# Stick_IMUinator_v2_1.net
KiCad netlist of a schematic drawn in EAGLE
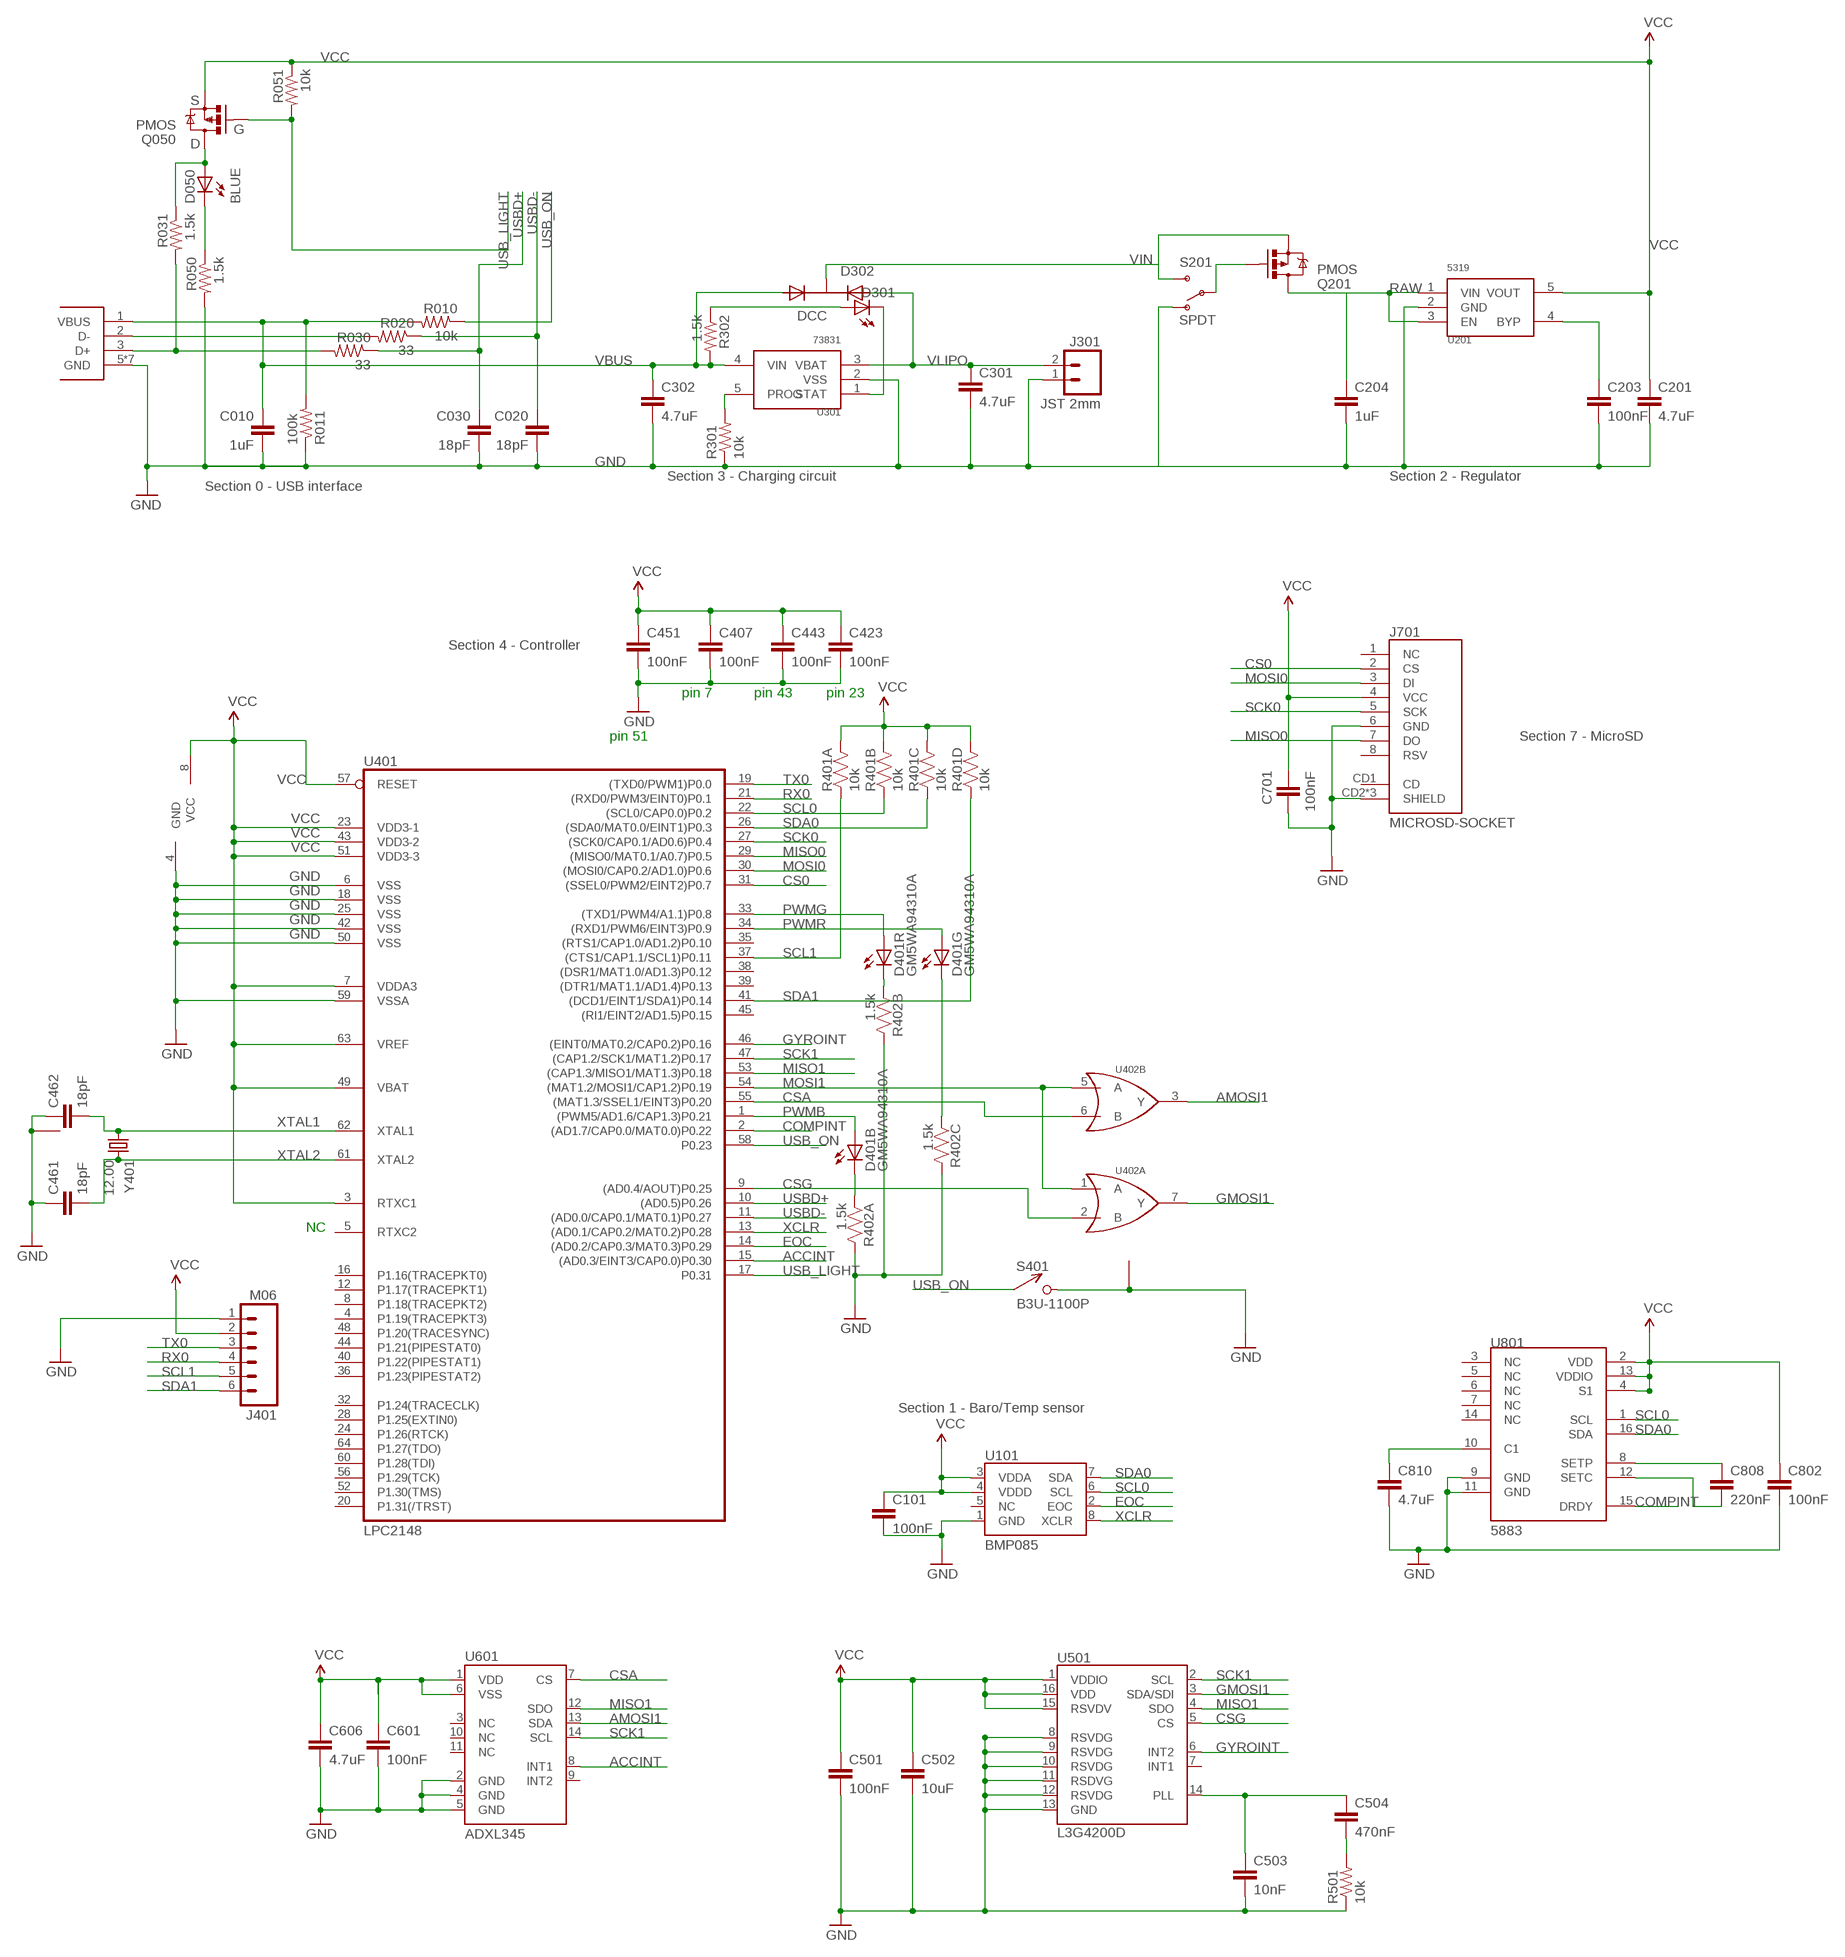
[diagram p0: schematic, sheet 1]

(export (version "E")
  (design (tool "Eeschema 10.0.6"))
  (components
    (comp (ref "C010")
      (value "1uF")
      (footprint "eagle-import:0402-CAP")
      (libsource (lib "eagle-import") (part "CAP0402-CAP"))
    )
    (comp (ref "C020")
      (value "18pF")
      (footprint "eagle-import:0402-CAP")
      (libsource (lib "eagle-import") (part "CAP0402-CAP"))
    )
    (comp (ref "C030")
      (value "18pF")
      (footprint "eagle-import:0402-CAP")
      (libsource (lib "eagle-import") (part "CAP0402-CAP"))
    )
    (comp (ref "C101")
      (value "100nF")
      (footprint "eagle-import:0402-CAP")
      (libsource (lib "eagle-import") (part "CAP0402-CAP"))
    )
    (comp (ref "C201")
      (value "4.7uF")
      (footprint "eagle-import:0402-CAP")
      (libsource (lib "eagle-import") (part "CAP0402-CAP"))
    )
    (comp (ref "C203")
      (value "100nF")
      (footprint "eagle-import:0402-CAP")
      (libsource (lib "eagle-import") (part "CAP0402-CAP"))
    )
    (comp (ref "C204")
      (value "1uF")
      (footprint "eagle-import:0402-CAP")
      (libsource (lib "eagle-import") (part "CAP0402-CAP"))
    )
    (comp (ref "C301")
      (value "4.7uF")
      (footprint "eagle-import:0402-CAP")
      (libsource (lib "eagle-import") (part "CAP0402-CAP"))
    )
    (comp (ref "C302")
      (value "4.7uF")
      (footprint "eagle-import:0402-CAP")
      (libsource (lib "eagle-import") (part "CAP0402-CAP"))
    )
    (comp (ref "C407")
      (value "100nF")
      (footprint "eagle-import:0402-CAP")
      (libsource (lib "eagle-import") (part "CAP0402-CAP"))
    )
    (comp (ref "C423")
      (value "100nF")
      (footprint "eagle-import:0402-CAP")
      (libsource (lib "eagle-import") (part "CAP0402-CAP"))
    )
    (comp (ref "C443")
      (value "100nF")
      (footprint "eagle-import:0402-CAP")
      (libsource (lib "eagle-import") (part "CAP0402-CAP"))
    )
    (comp (ref "C451")
      (value "100nF")
      (footprint "eagle-import:0402-CAP")
      (libsource (lib "eagle-import") (part "CAP0402-CAP"))
    )
    (comp (ref "C461")
      (value "18pF")
      (footprint "eagle-import:0402-CAP")
      (libsource (lib "eagle-import") (part "CAP0402-CAP"))
    )
    (comp (ref "C462")
      (value "18pF")
      (footprint "eagle-import:0402-CAP")
      (libsource (lib "eagle-import") (part "CAP0402-CAP"))
    )
    (comp (ref "C501")
      (value "100nF")
      (footprint "eagle-import:0402-CAP")
      (libsource (lib "eagle-import") (part "CAP0402-CAP"))
    )
    (comp (ref "C502")
      (value "10uF")
      (footprint "eagle-import:0603-CAP")
      (libsource (lib "eagle-import") (part "CAP0603-CAP"))
    )
    (comp (ref "C503")
      (value "10nF")
      (footprint "eagle-import:0402-CAP")
      (libsource (lib "eagle-import") (part "CAP0402-CAP"))
    )
    (comp (ref "C504")
      (value "470nF")
      (footprint "eagle-import:0402-CAP")
      (libsource (lib "eagle-import") (part "CAP0402-CAP"))
    )
    (comp (ref "C601")
      (value "100nF")
      (footprint "eagle-import:0402-CAP")
      (libsource (lib "eagle-import") (part "CAP0402-CAP"))
    )
    (comp (ref "C606")
      (value "4.7uF")
      (footprint "eagle-import:0402-CAP")
      (libsource (lib "eagle-import") (part "CAP0402-CAP"))
    )
    (comp (ref "C701")
      (value "100nF")
      (footprint "eagle-import:0402-CAP")
      (libsource (lib "eagle-import") (part "CAP0402-CAP"))
    )
    (comp (ref "C802")
      (value "100nF")
      (footprint "eagle-import:0402-CAP")
      (libsource (lib "eagle-import") (part "CAP0402-CAP"))
    )
    (comp (ref "C808")
      (value "220nF")
      (footprint "eagle-import:0402-CAP")
      (libsource (lib "eagle-import") (part "CAP0402-CAP"))
    )
    (comp (ref "C810")
      (value "4.7uF")
      (footprint "eagle-import:0402-CAP")
      (libsource (lib "eagle-import") (part "CAP0402-CAP"))
    )
    (comp (ref "D050")
      (value "BLUE")
      (footprint "eagle-import:LED-0603")
      (libsource (lib "eagle-import") (part "LED0603"))
    )
    (comp (ref "D301")
      (value "YELLOW")
      (footprint "eagle-import:LED-0603")
      (libsource (lib "eagle-import") (part "LED0603"))
    )
    (comp (ref "D302")
      (value "DCC")
      (footprint "eagle-import:SOT-23-3")
      (libsource (lib "eagle-import") (part "PMEG2005CT"))
    )
    (comp (ref "D401")
      (value "GM5WA94310A")
      (footprint "eagle-import:GM5WA94310A")
      (fields (field (name "DIGIKEY") "425-2728-1-ND"))
      (libsource (lib "eagle-import") (part "GM5WA94310A"))
    )
    (comp (ref "J001")
      (value "USB_MICROB_JST")
      (footprint "eagle-import:UB-MC5BR3-SD204-4S")
      (libsource (lib "eagle-import") (part "USB_MICROB_JST"))
    )
    (comp (ref "J301")
      (value "JST 2mm")
      (footprint "eagle-import:JST-2-SMD")
      (libsource (lib "eagle-import") (part "M02-JST-2MM-SMT"))
    )
    (comp (ref "J401")
      (value "M06")
      (footprint "eagle-import:1X06_LOCK")
      (libsource (lib "eagle-import") (part "M06LOCK"))
    )
    (comp (ref "J701")
      (value "MICROSD-SOCKET")
      (footprint "eagle-import:MICROSD-SOCKET-PP")
      (libsource (lib "eagle-import") (part "MICROSD-SOCKET"))
    )
    (comp (ref "Q050")
      (value "PMOS")
      (footprint "eagle-import:SOT23-3")
      (libsource (lib "eagle-import") (part "MOSFET-PCHANNELSMD"))
    )
    (comp (ref "Q201")
      (value "PMOS")
      (footprint "eagle-import:SOT23-3")
      (libsource (lib "eagle-import") (part "MOSFET-PCHANNELSMD"))
    )
    (comp (ref "R010")
      (value "10k")
      (footprint "eagle-import:0402-RES")
      (libsource (lib "eagle-import") (part "RESISTOR0402-RES"))
    )
    (comp (ref "R011")
      (value "100k")
      (footprint "eagle-import:0402-RES")
      (libsource (lib "eagle-import") (part "RESISTOR0402-RES"))
    )
    (comp (ref "R020")
      (value "33")
      (footprint "eagle-import:0402-RES")
      (libsource (lib "eagle-import") (part "RESISTOR0402-RES"))
    )
    (comp (ref "R030")
      (value "33")
      (footprint "eagle-import:0402-RES")
      (libsource (lib "eagle-import") (part "RESISTOR0402-RES"))
    )
    (comp (ref "R031")
      (value "1.5k")
      (footprint "eagle-import:0402-RES")
      (libsource (lib "eagle-import") (part "RESISTOR0402-RES"))
    )
    (comp (ref "R050")
      (value "1.5k")
      (footprint "eagle-import:0402-RES")
      (libsource (lib "eagle-import") (part "RESISTOR0402-RES"))
    )
    (comp (ref "R051")
      (value "10k")
      (footprint "eagle-import:0402-RES")
      (libsource (lib "eagle-import") (part "RESISTOR0402-RES"))
    )
    (comp (ref "R301")
      (value "10k")
      (footprint "eagle-import:0402-RES")
      (libsource (lib "eagle-import") (part "RESISTOR0402-RES"))
    )
    (comp (ref "R302")
      (value "1.5k")
      (footprint "eagle-import:0402-RES")
      (libsource (lib "eagle-import") (part "RESISTOR0402-RES"))
    )
    (comp (ref "R401")
      (value "10k")
      (footprint "eagle-import:CRA04")
      (fields (field (name "DIGIKEY") "CRA4S810KCT-ND"))
      (libsource (lib "eagle-import") (part "RP404"))
    )
    (comp (ref "R402")
      (value "1.5k")
      (footprint "eagle-import:CRA04")
      (fields (field (name "DIGIKEY") "CRA4S81.5KCT-ND"))
      (libsource (lib "eagle-import") (part "RP404"))
    )
    (comp (ref "R501")
      (value "10k")
      (footprint "eagle-import:0402-RES")
      (libsource (lib "eagle-import") (part "RESISTOR0402-RES"))
    )
    (comp (ref "S201")
      (value "SPDT")
      (footprint "eagle-import:AYZ0202")
      (libsource (lib "eagle-import") (part "SWITCH-SPSTSMD"))
    )
    (comp (ref "S401")
      (value "B3U-1100P")
      (footprint "eagle-import:B3U-1100P")
      (fields (field (name "DIGIKEY") "SW1021CT-ND"))
      (libsource (lib "eagle-import") (part "B3U-1100P"))
    )
    (comp (ref "U101")
      (value "BMP085")
      (footprint "eagle-import:BMP085")
      (libsource (lib "eagle-import") (part "BMP085"))
    )
    (comp (ref "U201")
      (value "5319")
      (footprint "eagle-import:SOT-23-5")
      (libsource (lib "eagle-import") (part "MIC5319D5"))
    )
    (comp (ref "U301")
      (value "73831")
      (footprint "eagle-import:SOT-23-5")
      (libsource (lib "eagle-import") (part "MCP73831"))
    )
    (comp (ref "U401")
      (value "LPC2148")
      (footprint "eagle-import:SQFP-S-10X10-64")
      (libsource (lib "eagle-import") (part "LPC213X"))
    )
    (comp (ref "U402")
      (value "7432")
      (footprint "eagle-import:DCU_8")
      (fields (field (name "DIGIKEY") "296-13268-1-ND"))
      (libsource (lib "eagle-import") (part "SN74LVC2G32"))
    )
    (comp (ref "U501")
      (value "L3G4200D")
      (footprint "eagle-import:LGA16-4X4")
      (libsource (lib "eagle-import") (part "L3G4200D"))
    )
    (comp (ref "U601")
      (value "ADXL345")
      (footprint "eagle-import:LGA14")
      (libsource (lib "eagle-import") (part "ADXL345"))
    )
    (comp (ref "U801")
      (value "5883")
      (footprint "eagle-import:16LPCC")
      (libsource (lib "eagle-import") (part "HMC5883LSMD"))
    )
    (comp (ref "Y401")
      (value "12.00")
      (footprint "eagle-import:CRYSTAL_SMD")
      (fields (field (name "DIGIKEY") "887-1316-1-ND"))
      (libsource (lib "eagle-import") (part "TSX-3225"))
    )
  )
  (nets
    (net (code "1") (name "/ACCINT") (class "Default")
      (node (ref "U401") (pin "15") (pinfunction "(AD0.3/EINT3/CAP0.0)P0.30_15") (pintype "bidirectional"))
      (node (ref "U601") (pin "8") (pinfunction "INT1_8") (pintype "bidirectional"))
    )
    (net (code "2") (name "/AMOSI1") (class "Default")
      (node (ref "U402") (pin "3") (pinfunction "Y_3") (pintype "bidirectional"))
      (node (ref "U601") (pin "13") (pinfunction "SDA_13") (pintype "bidirectional"))
    )
    (net (code "3") (name "/COMPINT") (class "Default")
      (node (ref "U401") (pin "2") (pinfunction "(AD1.7/CAP0.0/MAT0.0)P0.22_2") (pintype "bidirectional"))
      (node (ref "U801") (pin "15") (pinfunction "DRDY_15") (pintype "bidirectional"))
    )
    (net (code "4") (name "/CS0") (class "Default")
      (node (ref "J701") (pin "2") (pinfunction "CS_2") (pintype "bidirectional"))
      (node (ref "U401") (pin "31") (pinfunction "(SSEL0/PWM2/EINT2)P0.7_31") (pintype "bidirectional"))
    )
    (net (code "5") (name "/CSA") (class "Default")
      (node (ref "U401") (pin "55") (pinfunction "(MAT1.3/SSEL1/EINT3)P0.20_55") (pintype "bidirectional"))
      (node (ref "U402") (pin "6") (pinfunction "B_6") (pintype "bidirectional"))
      (node (ref "U601") (pin "7") (pinfunction "CS_7") (pintype "bidirectional"))
    )
    (net (code "6") (name "/CSG") (class "Default")
      (node (ref "U401") (pin "9") (pinfunction "(AD0.4/AOUT)P0.25_9") (pintype "bidirectional"))
      (node (ref "U402") (pin "2") (pinfunction "B_2") (pintype "bidirectional"))
      (node (ref "U501") (pin "5") (pinfunction "CS_5") (pintype "bidirectional"))
    )
    (net (code "7") (name "/EOC") (class "Default")
      (node (ref "U101") (pin "2") (pinfunction "EOC_2") (pintype "output"))
      (node (ref "U401") (pin "14") (pinfunction "(AD0.2/CAP0.3/MAT0.3)P0.29_14") (pintype "bidirectional"))
    )
    (net (code "8") (name "/GMOSI1") (class "Default")
      (node (ref "U402") (pin "7") (pinfunction "Y_7") (pintype "bidirectional"))
      (node (ref "U501") (pin "3") (pinfunction "SDA/SDI_3") (pintype "bidirectional"))
    )
    (net (code "9") (name "/GYROINT") (class "Default")
      (node (ref "U401") (pin "46") (pinfunction "(EINT0/MAT0.2/CAP0.2)P0.16_46") (pintype "bidirectional"))
      (node (ref "U501") (pin "6") (pinfunction "INT2_6") (pintype "bidirectional"))
    )
    (net (code "10") (name "/MISO0") (class "Default")
      (node (ref "J701") (pin "7") (pinfunction "DO_7") (pintype "bidirectional"))
      (node (ref "U401") (pin "29") (pinfunction "(MISO0/MAT0.1/A0.7)P0.5_29") (pintype "bidirectional"))
    )
    (net (code "11") (name "/MISO1") (class "Default")
      (node (ref "U401") (pin "53") (pinfunction "(CAP1.3/MISO1/MAT1.3)P0.18_53") (pintype "bidirectional"))
      (node (ref "U501") (pin "4") (pinfunction "SDO_4") (pintype "bidirectional"))
      (node (ref "U601") (pin "12") (pinfunction "SDO_12") (pintype "bidirectional"))
    )
    (net (code "12") (name "/MOSI0") (class "Default")
      (node (ref "J701") (pin "3") (pinfunction "DI_3") (pintype "bidirectional"))
      (node (ref "U401") (pin "30") (pinfunction "(MOSI0/CAP0.2/AD1.0)P0.6_30") (pintype "bidirectional"))
    )
    (net (code "13") (name "/MOSI1") (class "Default")
      (node (ref "U401") (pin "54") (pinfunction "(MAT1.2/MOSI1/CAP1.2)P0.19_54") (pintype "bidirectional"))
      (node (ref "U402") (pin "1") (pinfunction "A_1") (pintype "bidirectional"))
      (node (ref "U402") (pin "5") (pinfunction "A_5") (pintype "bidirectional"))
    )
    (net (code "14") (name "/PWMB") (class "Default")
      (node (ref "D401") (pin "1") (pinfunction "A_1") (pintype "passive"))
      (node (ref "U401") (pin "1") (pinfunction "(PWM5/AD1.6/CAP1.3)P0.21_1") (pintype "bidirectional"))
    )
    (net (code "15") (name "/PWMG") (class "Default")
      (node (ref "D401") (pin "3") (pinfunction "A_3") (pintype "passive"))
      (node (ref "U401") (pin "34") (pinfunction "(RXD1/PWM6/EINT3)P0.9_34") (pintype "bidirectional"))
    )
    (net (code "16") (name "/PWMR") (class "Default")
      (node (ref "D401") (pin "2") (pinfunction "A_2") (pintype "passive"))
      (node (ref "U401") (pin "33") (pinfunction "(TXD1/PWM4/A1.1)P0.8_33") (pintype "bidirectional"))
    )
    (net (code "17") (name "/RAW") (class "Default")
      (node (ref "C204") (pin "1") (pinfunction "1_1") (pintype "passive"))
      (node (ref "Q201") (pin "3") (pinfunction "D_3") (pintype "passive"))
      (node (ref "U201") (pin "1") (pinfunction "VIN_1") (pintype "bidirectional"))
      (node (ref "U201") (pin "3") (pinfunction "EN_3") (pintype "bidirectional"))
    )
    (net (code "18") (name "/RX0") (class "Default")
      (node (ref "J401") (pin "4") (pinfunction "4_4") (pintype "passive"))
      (node (ref "U401") (pin "21") (pinfunction "(RXD0/PWM3/EINT0)P0.1_21") (pintype "bidirectional"))
    )
    (net (code "19") (name "/SCK0") (class "Default")
      (node (ref "J701") (pin "5") (pinfunction "SCK_5") (pintype "bidirectional"))
      (node (ref "U401") (pin "27") (pinfunction "(SCK0/CAP0.1/AD0.6)P0.4_27") (pintype "bidirectional"))
    )
    (net (code "20") (name "/SCK1") (class "Default")
      (node (ref "U401") (pin "47") (pinfunction "(CAP1.2/SCK1/MAT1.2)P0.17_47") (pintype "bidirectional"))
      (node (ref "U501") (pin "2") (pinfunction "SCL_2") (pintype "bidirectional"))
      (node (ref "U601") (pin "14") (pinfunction "SCL_14") (pintype "bidirectional"))
    )
    (net (code "21") (name "/SCL0") (class "Default")
      (node (ref "R401") (pin "2") (pinfunction "1_2") (pintype "passive"))
      (node (ref "U101") (pin "6") (pinfunction "SCL_6") (pintype "input"))
      (node (ref "U401") (pin "22") (pinfunction "(SCL0/CAP0.0)P0.2_22") (pintype "bidirectional"))
      (node (ref "U801") (pin "1") (pinfunction "SCL_1") (pintype "bidirectional"))
    )
    (net (code "22") (name "/SCL1") (class "Default")
      (node (ref "J401") (pin "5") (pinfunction "5_5") (pintype "passive"))
      (node (ref "R401") (pin "1") (pinfunction "1_1") (pintype "passive"))
      (node (ref "U401") (pin "37") (pinfunction "(CTS1/CAP1.1/SCL1)P0.11_37") (pintype "bidirectional"))
    )
    (net (code "23") (name "/SDA0") (class "Default")
      (node (ref "R401") (pin "3") (pinfunction "1_3") (pintype "passive"))
      (node (ref "U101") (pin "7") (pinfunction "SDA_7") (pintype "bidirectional"))
      (node (ref "U401") (pin "26") (pinfunction "(SDA0/MAT0.0/EINT1)P0.3_26") (pintype "bidirectional"))
      (node (ref "U801") (pin "16") (pinfunction "SDA_16") (pintype "bidirectional"))
    )
    (net (code "24") (name "/SDA1") (class "Default")
      (node (ref "J401") (pin "6") (pinfunction "6_6") (pintype "passive"))
      (node (ref "R401") (pin "4") (pinfunction "1_4") (pintype "passive"))
      (node (ref "U401") (pin "41") (pinfunction "(DCD1/EINT1/SDA1)P0.14_41") (pintype "bidirectional"))
    )
    (net (code "25") (name "/TX0") (class "Default")
      (node (ref "J401") (pin "3") (pinfunction "3_3") (pintype "passive"))
      (node (ref "U401") (pin "19") (pinfunction "(TXD0/PWM1)P0.0_19") (pintype "bidirectional"))
    )
    (net (code "26") (name "/USBD+") (class "Default")
      (node (ref "C030") (pin "1") (pinfunction "1_1") (pintype "passive"))
      (node (ref "R030") (pin "1") (pinfunction "1_1") (pintype "passive"))
      (node (ref "U401") (pin "10") (pinfunction "(AD0.5)P0.26_10") (pintype "bidirectional"))
    )
    (net (code "27") (name "/USBD-") (class "Default")
      (node (ref "C020") (pin "1") (pinfunction "1_1") (pintype "passive"))
      (node (ref "R020") (pin "1") (pinfunction "1_1") (pintype "passive"))
      (node (ref "U401") (pin "11") (pinfunction "(AD0.0/CAP0.1/MAT0.1)P0.27_11") (pintype "bidirectional"))
    )
    (net (code "28") (name "/USB_LIGHT") (class "Default")
      (node (ref "Q050") (pin "1") (pinfunction "G_1") (pintype "passive"))
      (node (ref "R051") (pin "2") (pinfunction "2_2") (pintype "passive"))
      (node (ref "U401") (pin "17") (pinfunction "P0.31_17") (pintype "output"))
    )
    (net (code "29") (name "/USB_ON") (class "Default")
      (node (ref "R010") (pin "1") (pinfunction "1_1") (pintype "passive"))
      (node (ref "S401") (pin "P$1") (pinfunction "1_P$1") (pintype "bidirectional"))
      (node (ref "U401") (pin "58") (pinfunction "P0.23_58") (pintype "bidirectional"))
    )
    (net (code "30") (name "/VBUS") (class "Default")
      (node (ref "C010") (pin "1") (pinfunction "1_1") (pintype "passive"))
      (node (ref "C302") (pin "1") (pinfunction "1_1") (pintype "passive"))
      (node (ref "D302") (pin "1") (pinfunction "A1_1") (pintype "passive"))
      (node (ref "J001") (pin "1") (pinfunction "VBUS_1") (pintype "bidirectional"))
      (node (ref "R010") (pin "2") (pinfunction "2_2") (pintype "passive"))
      (node (ref "R011") (pin "2") (pinfunction "2_2") (pintype "passive"))
      (node (ref "R302") (pin "2") (pinfunction "2_2") (pintype "passive"))
      (node (ref "U301") (pin "4") (pinfunction "VIN_4") (pintype "bidirectional"))
    )
    (net (code "31") (name "/VIN") (class "Default")
      (node (ref "D302") (pin "3") (pinfunction "K_3") (pintype "passive"))
      (node (ref "Q201") (pin "2") (pinfunction "S_2") (pintype "passive"))
      (node (ref "S201") (pin "3") (pinfunction "S_3") (pintype "passive"))
    )
    (net (code "32") (name "/VLIPO") (class "Default")
      (node (ref "C301") (pin "1") (pinfunction "1_1") (pintype "passive"))
      (node (ref "D302") (pin "2") (pinfunction "A2_2") (pintype "passive"))
      (node (ref "J301") (pin "2") (pinfunction "2_2") (pintype "passive"))
      (node (ref "U301") (pin "3") (pinfunction "VBAT_3") (pintype "bidirectional"))
    )
    (net (code "33") (name "/XCLR") (class "Default")
      (node (ref "U101") (pin "8") (pinfunction "XCLR_8") (pintype "input"))
      (node (ref "U401") (pin "13") (pinfunction "(AD0.1/CAP0.2/MAT0.2)P0.28_13") (pintype "bidirectional"))
    )
    (net (code "34") (name "/XTAL1") (class "Default")
      (node (ref "C462") (pin "2") (pinfunction "2_2") (pintype "passive"))
      (node (ref "U401") (pin "62") (pinfunction "XTAL1_62") (pintype "input"))
      (node (ref "Y401") (pin "1") (pinfunction "1_1") (pintype "passive"))
    )
    (net (code "35") (name "/XTAL2") (class "Default")
      (node (ref "C461") (pin "2") (pinfunction "2_2") (pintype "passive"))
      (node (ref "U401") (pin "61") (pinfunction "XTAL2_61") (pintype "output"))
      (node (ref "Y401") (pin "3") (pinfunction "2_3") (pintype "passive"))
    )
    (net (code "36") (name "GND") (class "Default")
      (node (ref "C010") (pin "2") (pinfunction "2_2") (pintype "passive"))
      (node (ref "C020") (pin "2") (pinfunction "2_2") (pintype "passive"))
      (node (ref "C030") (pin "2") (pinfunction "2_2") (pintype "passive"))
      (node (ref "C101") (pin "2") (pinfunction "2_2") (pintype "passive"))
      (node (ref "C201") (pin "2") (pinfunction "2_2") (pintype "passive"))
      (node (ref "C203") (pin "2") (pinfunction "2_2") (pintype "passive"))
      (node (ref "C204") (pin "2") (pinfunction "2_2") (pintype "passive"))
      (node (ref "C301") (pin "2") (pinfunction "2_2") (pintype "passive"))
      (node (ref "C302") (pin "2") (pinfunction "2_2") (pintype "passive"))
      (node (ref "C407") (pin "2") (pinfunction "2_2") (pintype "passive"))
      (node (ref "C423") (pin "2") (pinfunction "2_2") (pintype "passive"))
      (node (ref "C443") (pin "2") (pinfunction "2_2") (pintype "passive"))
      (node (ref "C451") (pin "2") (pinfunction "2_2") (pintype "passive"))
      (node (ref "C461") (pin "1") (pinfunction "1_1") (pintype "passive"))
      (node (ref "C462") (pin "1") (pinfunction "1_1") (pintype "passive"))
      (node (ref "C501") (pin "2") (pinfunction "2_2") (pintype "passive"))
      (node (ref "C502") (pin "2") (pinfunction "2_2") (pintype "passive"))
      (node (ref "C503") (pin "2") (pinfunction "2_2") (pintype "passive"))
      (node (ref "C601") (pin "2") (pinfunction "2_2") (pintype "passive"))
      (node (ref "C606") (pin "2") (pinfunction "2_2") (pintype "passive"))
      (node (ref "C701") (pin "2") (pinfunction "2_2") (pintype "passive"))
      (node (ref "C802") (pin "2") (pinfunction "2_2") (pintype "passive"))
      (node (ref "C810") (pin "2") (pinfunction "2_2") (pintype "passive"))
      (node (ref "J001") (pin "5") (pinfunction "GND_5") (pintype "bidirectional"))
      (node (ref "J001") (pin "P$10") (pinfunction "GND_P$10") (pintype "bidirectional"))
      (node (ref "J001") (pin "P$11") (pinfunction "GND_P$11") (pintype "bidirectional"))
      (node (ref "J001") (pin "P$6") (pinfunction "GND_P$6") (pintype "bidirectional"))
      (node (ref "J001") (pin "P$7") (pinfunction "GND_P$7") (pintype "bidirectional"))
      (node (ref "J001") (pin "P$8") (pinfunction "GND_P$8") (pintype "bidirectional"))
      (node (ref "J001") (pin "P$9") (pinfunction "GND_P$9") (pintype "bidirectional"))
      (node (ref "J301") (pin "1") (pinfunction "1_1") (pintype "passive"))
      (node (ref "J401") (pin "1") (pinfunction "1_1") (pintype "passive"))
      (node (ref "J701") (pin "6") (pinfunction "GND_6") (pintype "bidirectional"))
      (node (ref "J701") (pin "CD2") (pinfunction "SHIELD_CD2") (pintype "bidirectional"))
      (node (ref "J701") (pin "GND1") (pinfunction "SHIELD_GND1") (pintype "bidirectional"))
      (node (ref "J701") (pin "GND3") (pinfunction "SHIELD_GND3") (pintype "bidirectional"))
      (node (ref "R011") (pin "1") (pinfunction "1_1") (pintype "passive"))
      (node (ref "R050") (pin "2") (pinfunction "2_2") (pintype "passive"))
      (node (ref "R301") (pin "1") (pinfunction "1_1") (pintype "passive"))
      (node (ref "R402") (pin "6") (pinfunction "2_6") (pintype "passive"))
      (node (ref "R402") (pin "7") (pinfunction "2_7") (pintype "passive"))
      (node (ref "R402") (pin "8") (pinfunction "2_8") (pintype "passive"))
      (node (ref "R501") (pin "1") (pinfunction "1_1") (pintype "passive"))
      (node (ref "S201") (pin "1") (pinfunction "O_1") (pintype "passive"))
      (node (ref "S401") (pin "P$2") (pinfunction "2_P$2") (pintype "bidirectional"))
      (node (ref "S401") (pin "P$3") (pinfunction "1_P$3") (pintype "bidirectional"))
      (node (ref "U101") (pin "1") (pinfunction "GND_1") (pintype "power_in"))
      (node (ref "U201") (pin "2") (pinfunction "GND_2") (pintype "bidirectional"))
      (node (ref "U301") (pin "2") (pinfunction "VSS_2") (pintype "bidirectional"))
      (node (ref "U401") (pin "18") (pinfunction "VSS_18") (pintype "power_in"))
      (node (ref "U401") (pin "25") (pinfunction "VSS_25") (pintype "power_in"))
      (node (ref "U401") (pin "42") (pinfunction "VSS_42") (pintype "power_in"))
      (node (ref "U401") (pin "50") (pinfunction "VSS_50") (pintype "power_in"))
      (node (ref "U401") (pin "59") (pinfunction "VSSA_59") (pintype "power_in"))
      (node (ref "U401") (pin "6") (pinfunction "VSS_6") (pintype "power_in"))
      (node (ref "U402") (pin "4") (pinfunction "GND_4") (pintype "bidirectional"))
      (node (ref "U501") (pin "10") (pinfunction "RSVDG_10") (pintype "bidirectional"))
      (node (ref "U501") (pin "11") (pinfunction "RSDVG_11") (pintype "bidirectional"))
      (node (ref "U501") (pin "12") (pinfunction "RSVDG_12") (pintype "bidirectional"))
      (node (ref "U501") (pin "13") (pinfunction "GND_13") (pintype "bidirectional"))
      (node (ref "U501") (pin "8") (pinfunction "RSVDG_8") (pintype "bidirectional"))
      (node (ref "U501") (pin "9") (pinfunction "RSVDG_9") (pintype "bidirectional"))
      (node (ref "U601") (pin "2") (pinfunction "GND_2") (pintype "bidirectional"))
      (node (ref "U601") (pin "4") (pinfunction "GND_4") (pintype "bidirectional"))
      (node (ref "U601") (pin "5") (pinfunction "GND_5") (pintype "bidirectional"))
      (node (ref "U801") (pin "11") (pinfunction "GND_11") (pintype "bidirectional"))
      (node (ref "U801") (pin "9") (pinfunction "GND_9") (pintype "bidirectional"))
      (node (ref "Y401") (pin "2") (pinfunction "1_2") (pintype "bidirectional"))
      (node (ref "Y401") (pin "4") (pinfunction "1_4") (pintype "bidirectional"))
    )
    (net (code "37") (name "Net-(C504-Pad2)") (class "Default")
      (node (ref "C504") (pin "2") (pinfunction "2_2") (pintype "passive"))
      (node (ref "R501") (pin "2") (pinfunction "2_2") (pintype "passive"))
    )
    (net (code "38") (name "Net-(D050-PadC)") (class "Default")
      (node (ref "D050") (pin "C") (pinfunction "C_C") (pintype "passive"))
      (node (ref "R050") (pin "1") (pinfunction "1_1") (pintype "passive"))
    )
    (net (code "39") (name "Net-(D301-PadA)") (class "Default")
      (node (ref "D301") (pin "A") (pinfunction "A_A") (pintype "passive"))
      (node (ref "R302") (pin "1") (pinfunction "1_1") (pintype "passive"))
    )
    (net (code "40") (name "Net-(D401A-C)") (class "Default")
      (node (ref "D401") (pin "6") (pinfunction "C_6") (pintype "passive"))
      (node (ref "R402") (pin "1") (pinfunction "1_1") (pintype "passive"))
    )
    (net (code "41") (name "Net-(D401B-C)") (class "Default")
      (node (ref "D401") (pin "4") (pinfunction "C_4") (pintype "passive"))
      (node (ref "R402") (pin "3") (pinfunction "1_3") (pintype "passive"))
    )
    (net (code "42") (name "Net-(D401C-C)") (class "Default")
      (node (ref "D401") (pin "5") (pinfunction "C_5") (pintype "passive"))
      (node (ref "R402") (pin "2") (pinfunction "1_2") (pintype "passive"))
    )
    (net (code "43") (name "Net-(J001-D+)") (class "Default")
      (node (ref "J001") (pin "3") (pinfunction "D+_3") (pintype "bidirectional"))
      (node (ref "R030") (pin "2") (pinfunction "2_2") (pintype "passive"))
      (node (ref "R031") (pin "2") (pinfunction "2_2") (pintype "passive"))
    )
    (net (code "44") (name "Net-(J001-D-)") (class "Default")
      (node (ref "J001") (pin "2") (pinfunction "D-_2") (pintype "bidirectional"))
      (node (ref "R020") (pin "2") (pinfunction "2_2") (pintype "passive"))
    )
    (net (code "45") (name "Net-(Q050-D)") (class "Default")
      (node (ref "D050") (pin "A") (pinfunction "A_A") (pintype "passive"))
      (node (ref "Q050") (pin "3") (pinfunction "D_3") (pintype "passive"))
      (node (ref "R031") (pin "1") (pinfunction "1_1") (pintype "passive"))
    )
    (net (code "46") (name "Net-(Q201-G)") (class "Default")
      (node (ref "Q201") (pin "1") (pinfunction "G_1") (pintype "passive"))
      (node (ref "S201") (pin "2") (pinfunction "P_2") (pintype "passive"))
    )
    (net (code "47") (name "Net-(U201-BYP)") (class "Default")
      (node (ref "C203") (pin "1") (pinfunction "1_1") (pintype "passive"))
      (node (ref "U201") (pin "4") (pinfunction "BYP_4") (pintype "bidirectional"))
    )
    (net (code "48") (name "Net-(U301-PROG)") (class "Default")
      (node (ref "R301") (pin "2") (pinfunction "2_2") (pintype "passive"))
      (node (ref "U301") (pin "5") (pinfunction "PROG_5") (pintype "bidirectional"))
    )
    (net (code "49") (name "Net-(U301-STAT)") (class "Default")
      (node (ref "D301") (pin "C") (pinfunction "C_C") (pintype "passive"))
      (node (ref "U301") (pin "1") (pinfunction "STAT_1") (pintype "bidirectional"))
    )
    (net (code "50") (name "Net-(U501-PLL)") (class "Default")
      (node (ref "C503") (pin "1") (pinfunction "1_1") (pintype "passive"))
      (node (ref "C504") (pin "1") (pinfunction "1_1") (pintype "passive"))
      (node (ref "U501") (pin "14") (pinfunction "PLL_14") (pintype "bidirectional"))
    )
    (net (code "51") (name "Net-(U801-C1)") (class "Default")
      (node (ref "C810") (pin "1") (pinfunction "1_1") (pintype "passive"))
      (node (ref "U801") (pin "10") (pinfunction "C1_10") (pintype "bidirectional"))
    )
    (net (code "52") (name "Net-(U801-SETC)") (class "Default")
      (node (ref "C808") (pin "2") (pinfunction "2_2") (pintype "passive"))
      (node (ref "U801") (pin "12") (pinfunction "SETC_12") (pintype "bidirectional"))
    )
    (net (code "53") (name "Net-(U801-SETP)") (class "Default")
      (node (ref "C808") (pin "1") (pinfunction "1_1") (pintype "passive"))
      (node (ref "U801") (pin "8") (pinfunction "SETP_8") (pintype "bidirectional"))
    )
    (net (code "54") (name "VCC") (class "Default")
      (node (ref "C101") (pin "1") (pinfunction "1_1") (pintype "passive"))
      (node (ref "C201") (pin "1") (pinfunction "1_1") (pintype "passive"))
      (node (ref "C407") (pin "1") (pinfunction "1_1") (pintype "passive"))
      (node (ref "C423") (pin "1") (pinfunction "1_1") (pintype "passive"))
      (node (ref "C443") (pin "1") (pinfunction "1_1") (pintype "passive"))
      (node (ref "C451") (pin "1") (pinfunction "1_1") (pintype "passive"))
      (node (ref "C501") (pin "1") (pinfunction "1_1") (pintype "passive"))
      (node (ref "C502") (pin "1") (pinfunction "1_1") (pintype "passive"))
      (node (ref "C601") (pin "1") (pinfunction "1_1") (pintype "passive"))
      (node (ref "C606") (pin "1") (pinfunction "1_1") (pintype "passive"))
      (node (ref "C701") (pin "1") (pinfunction "1_1") (pintype "passive"))
      (node (ref "C802") (pin "1") (pinfunction "1_1") (pintype "passive"))
      (node (ref "J401") (pin "2") (pinfunction "2_2") (pintype "passive"))
      (node (ref "J701") (pin "4") (pinfunction "VCC_4") (pintype "bidirectional"))
      (node (ref "Q050") (pin "2") (pinfunction "S_2") (pintype "passive"))
      (node (ref "R051") (pin "1") (pinfunction "1_1") (pintype "passive"))
      (node (ref "R401") (pin "5") (pinfunction "2_5") (pintype "passive"))
      (node (ref "R401") (pin "6") (pinfunction "2_6") (pintype "passive"))
      (node (ref "R401") (pin "7") (pinfunction "2_7") (pintype "passive"))
      (node (ref "R401") (pin "8") (pinfunction "2_8") (pintype "passive"))
      (node (ref "U101") (pin "3") (pinfunction "VDDA_3") (pintype "power_in"))
      (node (ref "U101") (pin "4") (pinfunction "VDDD_4") (pintype "power_in"))
      (node (ref "U201") (pin "5") (pinfunction "VOUT_5") (pintype "bidirectional"))
      (node (ref "U401") (pin "23") (pinfunction "VDD3-1_23") (pintype "power_in"))
      (node (ref "U401") (pin "3") (pinfunction "RTXC1_3") (pintype "input"))
      (node (ref "U401") (pin "43") (pinfunction "VDD3-2_43") (pintype "power_in"))
      (node (ref "U401") (pin "49") (pinfunction "VBAT_49") (pintype "power_in"))
      (node (ref "U401") (pin "51") (pinfunction "VDD3-3_51") (pintype "power_in"))
      (node (ref "U401") (pin "57") (pinfunction "RESET_57") (pintype "input"))
      (node (ref "U401") (pin "63") (pinfunction "VREF_63") (pintype "input"))
      (node (ref "U401") (pin "7") (pinfunction "VDDA3_7") (pintype "power_in"))
      (node (ref "U402") (pin "8") (pinfunction "VCC_8") (pintype "bidirectional"))
      (node (ref "U501") (pin "1") (pinfunction "VDDIO_1") (pintype "bidirectional"))
      (node (ref "U501") (pin "15") (pinfunction "RSVDV_15") (pintype "bidirectional"))
      (node (ref "U501") (pin "16") (pinfunction "VDD_16") (pintype "bidirectional"))
      (node (ref "U601") (pin "1") (pinfunction "VDD_1") (pintype "bidirectional"))
      (node (ref "U601") (pin "6") (pinfunction "VSS_6") (pintype "bidirectional"))
      (node (ref "U801") (pin "13") (pinfunction "VDDIO_13") (pintype "bidirectional"))
      (node (ref "U801") (pin "2") (pinfunction "VDD_2") (pintype "bidirectional"))
      (node (ref "U801") (pin "4") (pinfunction "S1_4") (pintype "bidirectional"))
    )
    (net (code "55") (name "unconnected-(J701-CD-PadCD1)") (class "Default")
      (node (ref "J701") (pin "CD1") (pinfunction "CD_CD1") (pintype "bidirectional"))
    )
    (net (code "56") (name "unconnected-(J701-NC-Pad1)") (class "Default")
      (node (ref "J701") (pin "1") (pinfunction "NC_1") (pintype "bidirectional"))
    )
    (net (code "57") (name "unconnected-(J701-RSV-Pad8)") (class "Default")
      (node (ref "J701") (pin "8") (pinfunction "RSV_8") (pintype "bidirectional"))
    )
    (net (code "58") (name "unconnected-(U101-NC-Pad5)") (class "Default")
      (node (ref "U101") (pin "5") (pinfunction "NC_5") (pintype "bidirectional"))
    )
    (net (code "59") (name "unconnected-(U401-(DSR1{slash}MAT1.0{slash}AD1.3)P0.12-Pad38)") (class "Default")
      (node (ref "U401") (pin "38") (pinfunction "(DSR1/MAT1.0/AD1.3)P0.12_38") (pintype "bidirectional"))
    )
    (net (code "60") (name "unconnected-(U401-(DTR1{slash}MAT1.1{slash}AD1.4)P0.13-Pad39)") (class "Default")
      (node (ref "U401") (pin "39") (pinfunction "(DTR1/MAT1.1/AD1.4)P0.13_39") (pintype "bidirectional"))
    )
    (net (code "61") (name "unconnected-(U401-(RI1{slash}EINT2{slash}AD1.5)P0.15-Pad45)") (class "Default")
      (node (ref "U401") (pin "45") (pinfunction "(RI1/EINT2/AD1.5)P0.15_45") (pintype "bidirectional"))
    )
    (net (code "62") (name "unconnected-(U401-(RTS1{slash}CAP1.0{slash}AD1.2)P0.10-Pad35)") (class "Default")
      (node (ref "U401") (pin "35") (pinfunction "(RTS1/CAP1.0/AD1.2)P0.10_35") (pintype "bidirectional"))
    )
    (net (code "63") (name "unconnected-(U401-P1.16(TRACEPKT0)-Pad16)") (class "Default")
      (node (ref "U401") (pin "16") (pinfunction "P1.16(TRACEPKT0)_16") (pintype "bidirectional"))
    )
    (net (code "64") (name "unconnected-(U401-P1.17(TRACEPKT1)-Pad12)") (class "Default")
      (node (ref "U401") (pin "12") (pinfunction "P1.17(TRACEPKT1)_12") (pintype "bidirectional"))
    )
    (net (code "65") (name "unconnected-(U401-P1.18(TRACEPKT2)-Pad8)") (class "Default")
      (node (ref "U401") (pin "8") (pinfunction "P1.18(TRACEPKT2)_8") (pintype "bidirectional"))
    )
    (net (code "66") (name "unconnected-(U401-P1.19(TRACEPKT3)-Pad4)") (class "Default")
      (node (ref "U401") (pin "4") (pinfunction "P1.19(TRACEPKT3)_4") (pintype "bidirectional"))
    )
    (net (code "67") (name "unconnected-(U401-P1.20(TRACESYNC)-Pad48)") (class "Default")
      (node (ref "U401") (pin "48") (pinfunction "P1.20(TRACESYNC)_48") (pintype "bidirectional"))
    )
    (net (code "68") (name "unconnected-(U401-P1.21(PIPESTAT0)-Pad44)") (class "Default")
      (node (ref "U401") (pin "44") (pinfunction "P1.21(PIPESTAT0)_44") (pintype "bidirectional"))
    )
    (net (code "69") (name "unconnected-(U401-P1.22(PIPESTAT1)-Pad40)") (class "Default")
      (node (ref "U401") (pin "40") (pinfunction "P1.22(PIPESTAT1)_40") (pintype "bidirectional"))
    )
    (net (code "70") (name "unconnected-(U401-P1.23(PIPESTAT2)-Pad36)") (class "Default")
      (node (ref "U401") (pin "36") (pinfunction "P1.23(PIPESTAT2)_36") (pintype "bidirectional"))
    )
    (net (code "71") (name "unconnected-(U401-P1.24(TRACECLK)-Pad32)") (class "Default")
      (node (ref "U401") (pin "32") (pinfunction "P1.24(TRACECLK)_32") (pintype "bidirectional"))
    )
    (net (code "72") (name "unconnected-(U401-P1.25(EXTIN0)-Pad28)") (class "Default")
      (node (ref "U401") (pin "28") (pinfunction "P1.25(EXTIN0)_28") (pintype "bidirectional"))
    )
    (net (code "73") (name "unconnected-(U401-P1.26(RTCK)-Pad24)") (class "Default")
      (node (ref "U401") (pin "24") (pinfunction "P1.26(RTCK)_24") (pintype "bidirectional"))
    )
    (net (code "74") (name "unconnected-(U401-P1.27(TDO)-Pad64)") (class "Default")
      (node (ref "U401") (pin "64") (pinfunction "P1.27(TDO)_64") (pintype "bidirectional"))
    )
    (net (code "75") (name "unconnected-(U401-P1.28(TDI)-Pad60)") (class "Default")
      (node (ref "U401") (pin "60") (pinfunction "P1.28(TDI)_60") (pintype "bidirectional"))
    )
    (net (code "76") (name "unconnected-(U401-P1.29(TCK)-Pad56)") (class "Default")
      (node (ref "U401") (pin "56") (pinfunction "P1.29(TCK)_56") (pintype "bidirectional"))
    )
    (net (code "77") (name "unconnected-(U401-P1.30(TMS)-Pad52)") (class "Default")
      (node (ref "U401") (pin "52") (pinfunction "P1.30(TMS)_52") (pintype "bidirectional"))
    )
    (net (code "78") (name "unconnected-(U401-P1.31({slash}TRST)-Pad20)") (class "Default")
      (node (ref "U401") (pin "20") (pinfunction "P1.31(/TRST)_20") (pintype "bidirectional"))
    )
    (net (code "79") (name "unconnected-(U401-RTXC2-Pad5)") (class "Default")
      (node (ref "U401") (pin "5") (pinfunction "RTXC2_5") (pintype "output"))
    )
    (net (code "80") (name "unconnected-(U501-INT1-Pad7)") (class "Default")
      (node (ref "U501") (pin "7") (pinfunction "INT1_7") (pintype "bidirectional"))
    )
    (net (code "81") (name "unconnected-(U601-INT2-Pad9)") (class "Default")
      (node (ref "U601") (pin "9") (pinfunction "INT2_9") (pintype "bidirectional"))
    )
    (net (code "82") (name "unconnected-(U601-NC-Pad3)") (class "Default")
      (node (ref "U601") (pin "3") (pinfunction "NC_3") (pintype "bidirectional"))
    )
    (net (code "83") (name "unconnected-(U601-NC-Pad10)") (class "Default")
      (node (ref "U601") (pin "10") (pinfunction "NC_10") (pintype "bidirectional"))
    )
    (net (code "84") (name "unconnected-(U601-NC-Pad11)") (class "Default")
      (node (ref "U601") (pin "11") (pinfunction "NC_11") (pintype "bidirectional"))
    )
    (net (code "85") (name "unconnected-(U801-NC-Pad3)") (class "Default")
      (node (ref "U801") (pin "3") (pinfunction "NC_3") (pintype "bidirectional"))
    )
    (net (code "86") (name "unconnected-(U801-NC-Pad5)") (class "Default")
      (node (ref "U801") (pin "5") (pinfunction "NC_5") (pintype "bidirectional"))
    )
    (net (code "87") (name "unconnected-(U801-NC-Pad6)") (class "Default")
      (node (ref "U801") (pin "6") (pinfunction "NC_6") (pintype "bidirectional"))
    )
    (net (code "88") (name "unconnected-(U801-NC-Pad7)") (class "Default")
      (node (ref "U801") (pin "7") (pinfunction "NC_7") (pintype "bidirectional"))
    )
    (net (code "89") (name "unconnected-(U801-NC-Pad14)") (class "Default")
      (node (ref "U801") (pin "14") (pinfunction "NC_14") (pintype "bidirectional"))
    )
  )
)
